# CT310_B_V1_0.net
KiCad netlist of a schematic drawn in Altium Designer
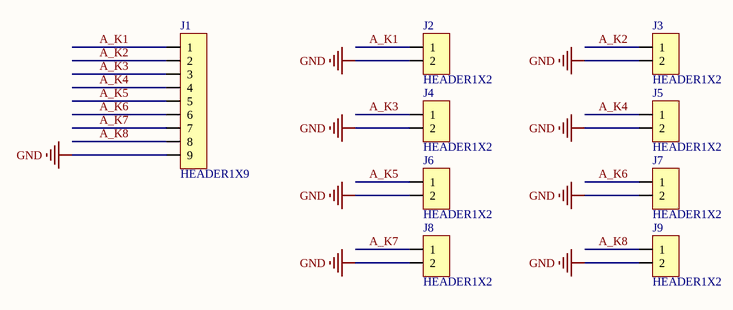
[diagram p0: CT310高端控制盒B区按键电路V1.0.SchDoc]

(export (version "E")
  (design (tool "Eeschema 10.0.6"))
  (components
    (comp (ref "J1")
      (value "HEADER1X9")
      (footprint "ZH1X9LT-1.5")
      (libsource (lib "Connector Class") (part "HEADER1X9"))
    )
    (comp (ref "J2")
      (value "HEADER1X2")
      (footprint "薄膜按键")
      (libsource (lib "Connector Class") (part "HEADER1X2"))
    )
    (comp (ref "J3")
      (value "HEADER1X2")
      (footprint "薄膜按键")
      (libsource (lib "Connector Class") (part "HEADER1X2"))
    )
    (comp (ref "J4")
      (value "HEADER1X2")
      (footprint "薄膜按键")
      (libsource (lib "Connector Class") (part "HEADER1X2"))
    )
    (comp (ref "J5")
      (value "HEADER1X2")
      (footprint "薄膜按键")
      (libsource (lib "Connector Class") (part "HEADER1X2"))
    )
    (comp (ref "J6")
      (value "HEADER1X2")
      (footprint "薄膜按键")
      (libsource (lib "Connector Class") (part "HEADER1X2"))
    )
    (comp (ref "J7")
      (value "HEADER1X2")
      (footprint "薄膜按键")
      (libsource (lib "Connector Class") (part "HEADER1X2"))
    )
    (comp (ref "J8")
      (value "HEADER1X2")
      (footprint "薄膜按键")
      (libsource (lib "Connector Class") (part "HEADER1X2"))
    )
    (comp (ref "J9")
      (value "HEADER1X2")
      (footprint "薄膜按键")
      (libsource (lib "Connector Class") (part "HEADER1X2"))
    )
  )
  (nets
    (net (code "1") (name "/A_K1") (class "Default")
      (node (ref "J1") (pin "1") (pinfunction "1_1") (pintype "passive"))
      (node (ref "J2") (pin "1") (pinfunction "1_1") (pintype "passive"))
    )
    (net (code "2") (name "/A_K2") (class "Default")
      (node (ref "J1") (pin "2") (pinfunction "2_2") (pintype "passive"))
      (node (ref "J3") (pin "1") (pinfunction "1_1") (pintype "passive"))
    )
    (net (code "3") (name "/A_K3") (class "Default")
      (node (ref "J1") (pin "3") (pinfunction "3_3") (pintype "passive"))
      (node (ref "J4") (pin "1") (pinfunction "1_1") (pintype "passive"))
    )
    (net (code "4") (name "/A_K4") (class "Default")
      (node (ref "J1") (pin "4") (pinfunction "4_4") (pintype "passive"))
      (node (ref "J5") (pin "1") (pinfunction "1_1") (pintype "passive"))
    )
    (net (code "5") (name "/A_K5") (class "Default")
      (node (ref "J1") (pin "5") (pinfunction "5_5") (pintype "passive"))
      (node (ref "J6") (pin "1") (pinfunction "1_1") (pintype "passive"))
    )
    (net (code "6") (name "/A_K6") (class "Default")
      (node (ref "J1") (pin "6") (pinfunction "6_6") (pintype "passive"))
      (node (ref "J7") (pin "1") (pinfunction "1_1") (pintype "passive"))
    )
    (net (code "7") (name "/A_K7") (class "Default")
      (node (ref "J1") (pin "7") (pinfunction "7_7") (pintype "passive"))
      (node (ref "J8") (pin "1") (pinfunction "1_1") (pintype "passive"))
    )
    (net (code "8") (name "/A_K8") (class "Default")
      (node (ref "J1") (pin "8") (pinfunction "8_8") (pintype "passive"))
      (node (ref "J9") (pin "1") (pinfunction "1_1") (pintype "passive"))
    )
    (net (code "9") (name "GND") (class "Default")
      (node (ref "J1") (pin "9") (pinfunction "9_9") (pintype "passive"))
      (node (ref "J2") (pin "2") (pinfunction "2_2") (pintype "passive"))
      (node (ref "J3") (pin "2") (pinfunction "2_2") (pintype "passive"))
      (node (ref "J4") (pin "2") (pinfunction "2_2") (pintype "passive"))
      (node (ref "J5") (pin "2") (pinfunction "2_2") (pintype "passive"))
      (node (ref "J6") (pin "2") (pinfunction "2_2") (pintype "passive"))
      (node (ref "J7") (pin "2") (pinfunction "2_2") (pintype "passive"))
      (node (ref "J8") (pin "2") (pinfunction "2_2") (pintype "passive"))
      (node (ref "J9") (pin "2") (pinfunction "2_2") (pintype "passive"))
    )
  )
)
